# RS485.net
KiCad netlist of a schematic drawn in Altium Designer
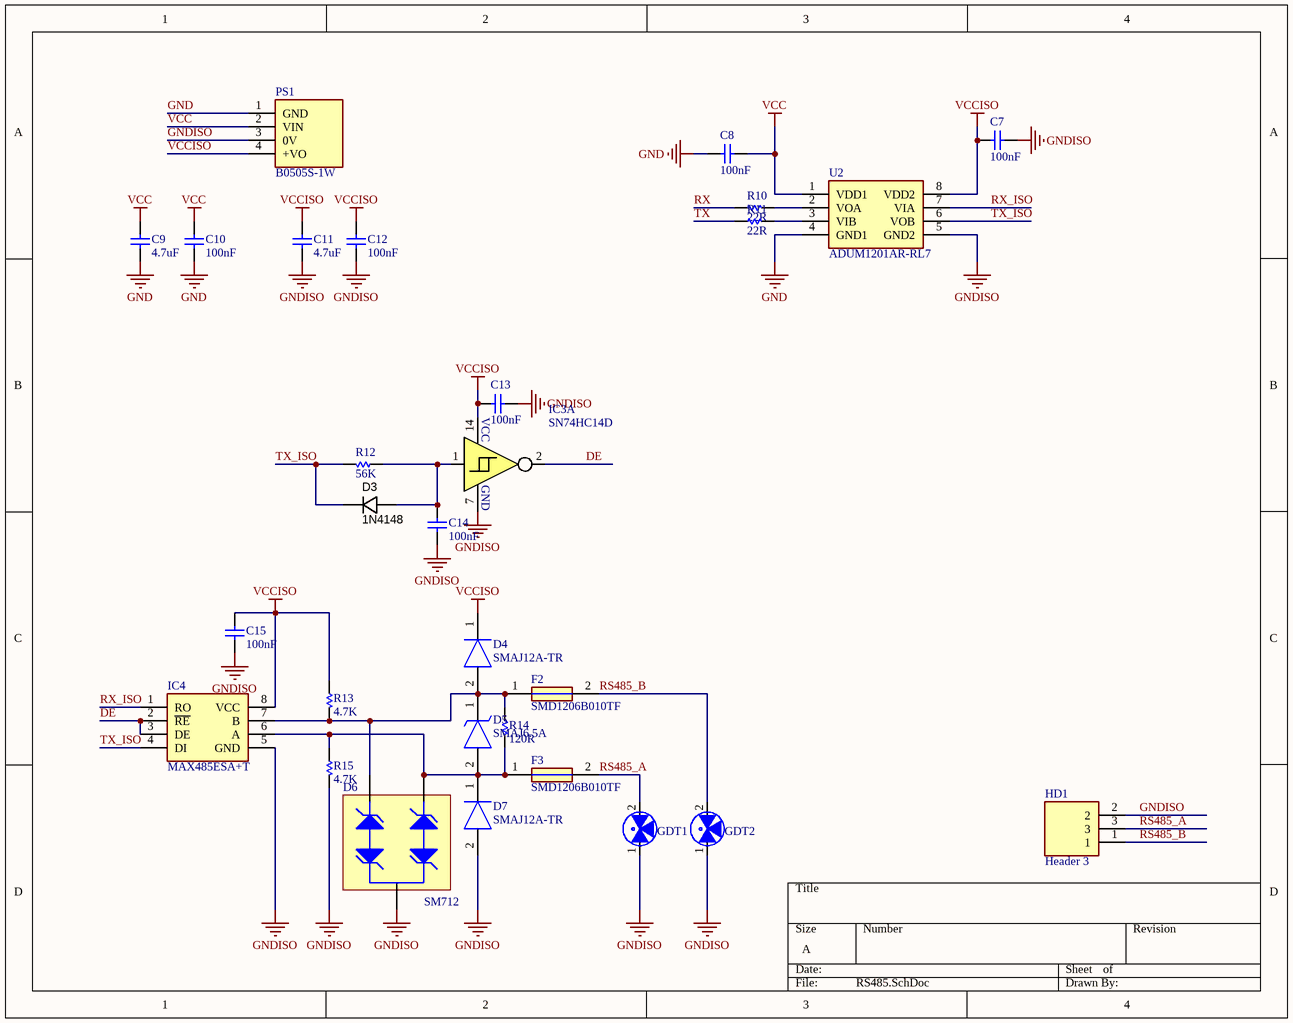
[diagram p0: RS485.SchDoc]

(export (version "E")
  (design (tool "Eeschema 10.0.6"))
  (components
    (comp (ref "C7")
      (value "100nF")
      (footprint "CAP-0603-Standard")
      (description "CAP-CER, SMD, 0603, 0.1UF")
      (fields
        (field (name "MANUFACTURER") "AVX")
        (field (name "MANUFACTURER PART NUMBER") "06031C104JAT2A")
        (field (name "CAPACITANCE") "100nF")
      )
      (libsource (lib "MRET_VSM") (part "CAP-0603-0.1uF"))
    )
    (comp (ref "C8")
      (value "100nF")
      (footprint "CAP-0603-Standard")
      (description "CAP-CER, SMD, 0603, 0.1UF")
      (fields
        (field (name "MANUFACTURER") "AVX")
        (field (name "MANUFACTURER PART NUMBER") "06031C104JAT2A")
        (field (name "CAPACITANCE") "100nF")
      )
      (libsource (lib "MRET_VSM") (part "CAP-0603-0.1uF"))
    )
    (comp (ref "C9")
      (value "4.7uF")
      (footprint "CAP-0603-Standard")
      (description "CAP-CER, SMD, 0603, 4.7UF, 5%, 100V")
      (fields
        (field (name "MANUFACTURER") "AVX")
        (field (name "MANUFACTURER PART NUMBER") "06031C104JAT2A")
        (field (name "CAPACITANCE") "4.7uF")
      )
      (libsource (lib "MRET_VSM") (part "CAP-0603-0.1uF"))
    )
    (comp (ref "C10")
      (value "100nF")
      (footprint "CAP-0603-Standard")
      (description "CAP-CER, SMD, 0603, 0.1UF")
      (fields
        (field (name "MANUFACTURER") "AVX")
        (field (name "MANUFACTURER PART NUMBER") "06031C104JAT2A")
        (field (name "CAPACITANCE") "100nF")
      )
      (libsource (lib "MRET_VSM") (part "CAP-0603-0.1uF"))
    )
    (comp (ref "C11")
      (value "4.7uF")
      (footprint "CAP-0603-Standard")
      (description "CAP-CER, SMD, 0603, 4.7UF, 5%, 100V")
      (fields
        (field (name "MANUFACTURER") "AVX")
        (field (name "MANUFACTURER PART NUMBER") "06031C104JAT2A")
        (field (name "CAPACITANCE") "4.7uF")
      )
      (libsource (lib "MRET_VSM") (part "CAP-0603-0.1uF"))
    )
    (comp (ref "C12")
      (value "100nF")
      (footprint "CAP-0603-Standard")
      (description "CAP-CER, SMD, 0603, 0.1UF")
      (fields
        (field (name "MANUFACTURER") "AVX")
        (field (name "MANUFACTURER PART NUMBER") "06031C104JAT2A")
        (field (name "CAPACITANCE") "100nF")
      )
      (libsource (lib "MRET_VSM") (part "CAP-0603-0.1uF"))
    )
    (comp (ref "C13")
      (value "100nF")
      (footprint "CAP-0603-Standard")
      (description "CAP-CER, SMD, 0603, 0.1UF")
      (fields
        (field (name "MANUFACTURER") "AVX")
        (field (name "MANUFACTURER PART NUMBER") "06031C104JAT2A")
        (field (name "CAPACITANCE") "100nF")
      )
      (libsource (lib "MRET_VSM") (part "CAP-0603-0.1uF"))
    )
    (comp (ref "C14")
      (value "100nF")
      (footprint "CAP-0603-Standard")
      (description "CAP-CER, SMD, 0603, 0.1UF")
      (fields
        (field (name "MANUFACTURER") "AVX")
        (field (name "MANUFACTURER PART NUMBER") "06031C104JAT2A")
        (field (name "CAPACITANCE") "100nF")
      )
      (libsource (lib "MRET_VSM") (part "CAP-0603-0.1uF"))
    )
    (comp (ref "C15")
      (value "100nF")
      (footprint "CAP-0603-Standard")
      (description "CAP-CER, SMD, 0603, 0.1UF")
      (fields
        (field (name "MANUFACTURER") "AVX")
        (field (name "MANUFACTURER PART NUMBER") "06031C104JAT2A")
        (field (name "CAPACITANCE") "100nF")
      )
      (libsource (lib "MRET_VSM") (part "CAP-0603-0.1uF"))
    )
    (comp (ref "D3")
      (value "1N4148")
      (footprint "SOD523F")
      (description "Diode SMD small signal 0.2A SOD-523F")
      (libsource (lib "PBL - Diodes") (part "DIODE_1N4148_200mA_SOD523F"))
    )
    (comp (ref "D4")
      (value "SMAJ12A-TR")
      (footprint "SamacSys:DIOM5126X265N")
      (description "Diode")
      (fields (field (name "MOUSER PART NUMBER") "511-SMAJ12A-TR"))
      (libsource (lib "*") (part "SMAJ12A-TR"))
    )
    (comp (ref "D5")
      (value "SMAJ6.5A")
      (footprint "SamacSys:DIOM5026X229N")
      (description "TVS Diode (Uni-directional)")
      (fields (field (name "MOUSER PART NUMBER") "576-SMAJ6.5A"))
      (libsource (lib "*") (part "SMAJ6.5A"))
    )
    (comp (ref "D6")
      (value "SM712")
      (footprint "SOT23")
      (description "TVS DIODE 7VWM/12VWM SOT23")
      (fields
        (field (name "MANUFACTURER") "Bourns Inc.")
        (field (name "MANUFACTURER PART NUMBER") "CDSOT23-SM712")
      )
      (libsource (lib "GremsyCo") (part "CDSOT23-SM712"))
    )
    (comp (ref "D7")
      (value "SMAJ12A-TR")
      (footprint "SamacSys:DIOM5126X265N")
      (description "Diode")
      (fields (field (name "MOUSER PART NUMBER") "511-SMAJ12A-TR"))
      (libsource (lib "*") (part "SMAJ12A-TR"))
    )
    (comp (ref "F2")
      (value "SMD1206B010TF")
      (footprint "SamacSys:FUSC3216X100N")
      (description "Fuse")
      (fields
        (field (name "MANUFACTURER_PART_NUMBER") "1206L020YR")
        (field (name "MOUSER PART NUMBER") "576-1206L020YR")
      )
      (libsource (lib "*") (part "1206L020YR"))
    )
    (comp (ref "F3")
      (value "SMD1206B010TF")
      (footprint "SamacSys:FUSC3216X100N")
      (description "Fuse")
      (fields
        (field (name "MANUFACTURER_PART_NUMBER") "1206L020YR")
        (field (name "MOUSER PART NUMBER") "576-1206L020YR")
      )
      (libsource (lib "*") (part "1206L020YR"))
    )
    (comp (ref "GDT1")
      (value "2RL150M-5")
      (footprint "2R-5-ST5")
      (description "GDT 150V 5KA 2 POLE SMD")
      (libsource (lib "MRET_VSM") (part "2RL150M-5"))
    )
    (comp (ref "GDT2")
      (value "2RL150M-5")
      (footprint "2R-5-ST5")
      (description "GDT 150V 5KA 2 POLE SMD")
      (libsource (lib "MRET_VSM") (part "2RL150M-5"))
    )
    (comp (ref "HD1")
      (value "Header 3")
      (footprint "SamacSys:SHDRRA3W80P0X381_1X3_1190X920X720P")
      (description "Terminal Block Header, 3, 300 V, 12 A, 3.81 mm")
      (fields (field (name "MANUFACTURER_PART_NUMBER") "20020110-D031A01LF"))
      (libsource (lib "SamacSys") (part "Header 3"))
    )
    (comp (ref "IC3")
      (value "SN74HC14D")
      (footprint "SOIC127P600X175-14N")
      (description "Hex Schmitt Trigger")
      (libsource (lib "SamacSys") (part "SN74HC14D_1"))
    )
    (comp (ref "IC4")
      (value "MAX485ESA+T")
      (footprint "SamacSys:SOIC127P600X175-8N")
      (description "Integrated Circuit")
      (fields (field (name "MOUSER PART NUMBER") "700-MAX485ESAT"))
      (libsource (lib "*") (part "MAX485ESA+T"))
    )
    (comp (ref "PS1")
      (value "B0505S-1W")
      (footprint "SamacSys:B0505S1W")
      (description "Power Supply")
      (libsource (lib "*") (part "B0505S-1W"))
    )
    (comp (ref "R10")
      (value "22R")
      (footprint "RES-0603-STANDARD")
      (description "RES, SMD, 0603, 5%, 1/10W, THICK FILM")
      (fields
        (field (name "MANUFACTURER") "Yageo")
        (field (name "MANUFACTURER PART NUMBER") "AC0603FR-101KL")
        (field (name "RESISTANCE") "22R")
      )
      (libsource (lib "MRET_VSM") (part "RES-0603"))
    )
    (comp (ref "R11")
      (value "22R")
      (footprint "RES-0603-STANDARD")
      (description "RES, SMD, 0603, 5%, 1/10W, THICK FILM")
      (fields
        (field (name "MANUFACTURER") "Yageo")
        (field (name "MANUFACTURER PART NUMBER") "AC0603FR-101KL")
        (field (name "RESISTANCE") "22R")
      )
      (libsource (lib "MRET_VSM") (part "RES-0603"))
    )
    (comp (ref "R12")
      (value "56K")
      (footprint "RES-0603-STANDARD")
      (description "RES, SMD, 0603, 1%, 1/10W, THICK FILM")
      (fields
        (field (name "MANUFACTURER") "Yageo")
        (field (name "MANUFACTURER PART NUMBER") "AC0603FR-101KL")
        (field (name "RESISTANCE") "56K")
      )
      (libsource (lib "MRET_VSM") (part "RES-0603"))
    )
    (comp (ref "R13")
      (value "4.7K")
      (footprint "RES-0603-STANDARD")
      (description "RES, SMD, 0603, 5%, 1/10W, THICK FILM")
      (fields
        (field (name "MANUFACTURER") "Yageo")
        (field (name "MANUFACTURER PART NUMBER") "AC0603FR-101KL")
        (field (name "RESISTANCE") "4.7K")
      )
      (libsource (lib "MRET_VSM") (part "RES-0603"))
    )
    (comp (ref "R14")
      (value "120R")
      (footprint "RES-0603-STANDARD")
      (description "RES, SMD, 0603, 1%, 1/10W, THICK FILM")
      (fields
        (field (name "MANUFACTURER") "Yageo")
        (field (name "MANUFACTURER PART NUMBER") "AC0603FR-101KL")
        (field (name "RESISTANCE") "120R")
      )
      (libsource (lib "MRET_VSM") (part "RES-0603"))
    )
    (comp (ref "R15")
      (value "4.7K")
      (footprint "RES-0603-STANDARD")
      (description "RES, SMD, 0603, 5%, 1/10W, THICK FILM")
      (fields
        (field (name "MANUFACTURER") "Yageo")
        (field (name "MANUFACTURER PART NUMBER") "AC0603FR-101KL")
        (field (name "RESISTANCE") "4.7K")
      )
      (libsource (lib "MRET_VSM") (part "RES-0603"))
    )
    (comp (ref "U2")
      (value "ADUM1201AR-RL7")
      (footprint "SamacSys:SOIC127P600X175-8N")
      (description "Capacitor")
      (fields (field (name "MOUSER PART NUMBER") "584-ADUM1201AR-R7"))
      (libsource (lib "*") (part "ADUM1201AR-RL7"))
    )
  )
  (nets
    (net (code "1") (name "/DE") (class "Default")
      (node (ref "IC3") (pin "2") (pinfunction "1Y_2") (pintype "passive"))
      (node (ref "IC4") (pin "2") (pinfunction "~{RE}_2") (pintype "passive"))
      (node (ref "IC4") (pin "3") (pinfunction "DE_3") (pintype "passive"))
    )
    (net (code "2") (name "/RS485_A") (class "Default")
      (node (ref "F3") (pin "2") (pinfunction "2_2") (pintype "passive"))
      (node (ref "GDT1") (pin "2") (pinfunction "2_2") (pintype "passive"))
      (node (ref "HD1") (pin "3") (pinfunction "3_3") (pintype "passive"))
    )
    (net (code "3") (name "/RS485_B") (class "Default")
      (node (ref "F2") (pin "2") (pinfunction "2_2") (pintype "passive"))
      (node (ref "GDT2") (pin "2") (pinfunction "2_2") (pintype "passive"))
      (node (ref "HD1") (pin "1") (pinfunction "1_1") (pintype "passive"))
    )
    (net (code "4") (name "/RX") (class "Default")
      (node (ref "R10") (pin "1") (pinfunction "1_1") (pintype "passive"))
    )
    (net (code "5") (name "/RX_ISO") (class "Default")
      (node (ref "IC4") (pin "1") (pinfunction "RO_1") (pintype "passive"))
      (node (ref "U2") (pin "7") (pinfunction "VIA_7") (pintype "passive"))
    )
    (net (code "6") (name "/TX") (class "Default")
      (node (ref "R11") (pin "1") (pinfunction "1_1") (pintype "passive"))
    )
    (net (code "7") (name "/TX_ISO") (class "Default")
      (node (ref "D3") (pin "K") (pinfunction "K_K") (pintype "passive"))
      (node (ref "IC4") (pin "4") (pinfunction "DI_4") (pintype "passive"))
      (node (ref "R12") (pin "2") (pinfunction "2_2") (pintype "passive"))
      (node (ref "U2") (pin "6") (pinfunction "VOB_6") (pintype "passive"))
    )
    (net (code "8") (name "GND") (class "Default")
      (node (ref "C10") (pin "2") (pinfunction "2_2") (pintype "passive"))
      (node (ref "C8") (pin "2") (pinfunction "2_2") (pintype "passive"))
      (node (ref "C9") (pin "2") (pinfunction "2_2") (pintype "passive"))
      (node (ref "PS1") (pin "1") (pinfunction "GND_1") (pintype "passive"))
      (node (ref "U2") (pin "4") (pinfunction "GND1_4") (pintype "passive"))
    )
    (net (code "9") (name "GNDISO") (class "Default")
      (node (ref "C11") (pin "2") (pinfunction "2_2") (pintype "passive"))
      (node (ref "C12") (pin "2") (pinfunction "2_2") (pintype "passive"))
      (node (ref "C13") (pin "1") (pinfunction "1_1") (pintype "passive"))
      (node (ref "C14") (pin "2") (pinfunction "2_2") (pintype "passive"))
      (node (ref "C15") (pin "1") (pinfunction "1_1") (pintype "passive"))
      (node (ref "C7") (pin "1") (pinfunction "1_1") (pintype "passive"))
      (node (ref "D6") (pin "3") (pinfunction "3_3") (pintype "power_in"))
      (node (ref "D7") (pin "2") (pinfunction "A_2") (pintype "passive"))
      (node (ref "GDT1") (pin "1") (pinfunction "1_1") (pintype "passive"))
      (node (ref "GDT2") (pin "1") (pinfunction "1_1") (pintype "passive"))
      (node (ref "HD1") (pin "2") (pinfunction "2_2") (pintype "passive"))
      (node (ref "IC3") (pin "7") (pinfunction "GND_7") (pintype "power_in"))
      (node (ref "IC4") (pin "5") (pinfunction "GND_5") (pintype "passive"))
      (node (ref "PS1") (pin "3") (pinfunction "0V_3") (pintype "passive"))
      (node (ref "R15") (pin "2") (pinfunction "2_2") (pintype "passive"))
      (node (ref "U2") (pin "5") (pinfunction "GND2_5") (pintype "passive"))
    )
    (net (code "10") (name "Net-(D4-A)") (class "Default")
      (node (ref "D4") (pin "2") (pinfunction "A_2") (pintype "passive"))
      (node (ref "D5") (pin "1") (pinfunction "K_1") (pintype "passive"))
      (node (ref "D6") (pin "2") (pinfunction "2_2") (pintype "power_in"))
      (node (ref "F2") (pin "1") (pinfunction "1_1") (pintype "passive"))
      (node (ref "IC4") (pin "7") (pinfunction "B_7") (pintype "passive"))
      (node (ref "R13") (pin "2") (pinfunction "2_2") (pintype "passive"))
      (node (ref "R14") (pin "1") (pinfunction "1_1") (pintype "passive"))
    )
    (net (code "11") (name "Net-(D5-A)") (class "Default")
      (node (ref "D5") (pin "2") (pinfunction "A_2") (pintype "passive"))
      (node (ref "D6") (pin "1") (pinfunction "1_1") (pintype "power_in"))
      (node (ref "D7") (pin "1") (pinfunction "K_1") (pintype "passive"))
      (node (ref "F3") (pin "1") (pinfunction "1_1") (pintype "passive"))
      (node (ref "IC4") (pin "6") (pinfunction "A_6") (pintype "passive"))
      (node (ref "R14") (pin "2") (pinfunction "2_2") (pintype "passive"))
      (node (ref "R15") (pin "1") (pinfunction "1_1") (pintype "passive"))
    )
    (net (code "12") (name "Net-(IC3A-1A)") (class "Default")
      (node (ref "C14") (pin "1") (pinfunction "1_1") (pintype "passive"))
      (node (ref "D3") (pin "A") (pinfunction "A_A") (pintype "passive"))
      (node (ref "IC3") (pin "1") (pinfunction "1A_1") (pintype "passive"))
      (node (ref "R12") (pin "1") (pinfunction "1_1") (pintype "passive"))
    )
    (net (code "13") (name "Net-(U2-VIB)") (class "Default")
      (node (ref "R11") (pin "2") (pinfunction "2_2") (pintype "passive"))
      (node (ref "U2") (pin "3") (pinfunction "VIB_3") (pintype "passive"))
    )
    (net (code "14") (name "Net-(U2-VOA)") (class "Default")
      (node (ref "R10") (pin "2") (pinfunction "2_2") (pintype "passive"))
      (node (ref "U2") (pin "2") (pinfunction "VOA_2") (pintype "passive"))
    )
    (net (code "15") (name "VCC") (class "Default")
      (node (ref "C10") (pin "1") (pinfunction "1_1") (pintype "passive"))
      (node (ref "C8") (pin "1") (pinfunction "1_1") (pintype "passive"))
      (node (ref "C9") (pin "1") (pinfunction "1_1") (pintype "passive"))
      (node (ref "PS1") (pin "2") (pinfunction "VIN_2") (pintype "passive"))
      (node (ref "U2") (pin "1") (pinfunction "VDD1_1") (pintype "passive"))
    )
    (net (code "16") (name "VCCISO") (class "Default")
      (node (ref "C11") (pin "1") (pinfunction "1_1") (pintype "passive"))
      (node (ref "C12") (pin "1") (pinfunction "1_1") (pintype "passive"))
      (node (ref "C13") (pin "2") (pinfunction "2_2") (pintype "passive"))
      (node (ref "C15") (pin "2") (pinfunction "2_2") (pintype "passive"))
      (node (ref "C7") (pin "2") (pinfunction "2_2") (pintype "passive"))
      (node (ref "D4") (pin "1") (pinfunction "K_1") (pintype "passive"))
      (node (ref "IC3") (pin "14") (pinfunction "VCC_14") (pintype "power_in"))
      (node (ref "IC4") (pin "8") (pinfunction "VCC_8") (pintype "passive"))
      (node (ref "PS1") (pin "4") (pinfunction "+VO_4") (pintype "passive"))
      (node (ref "R13") (pin "1") (pinfunction "1_1") (pintype "passive"))
      (node (ref "U2") (pin "8") (pinfunction "VDD2_8") (pintype "passive"))
    )
  )
)
